# emmc.net
KiCad netlist of a schematic drawn in Altium Designer
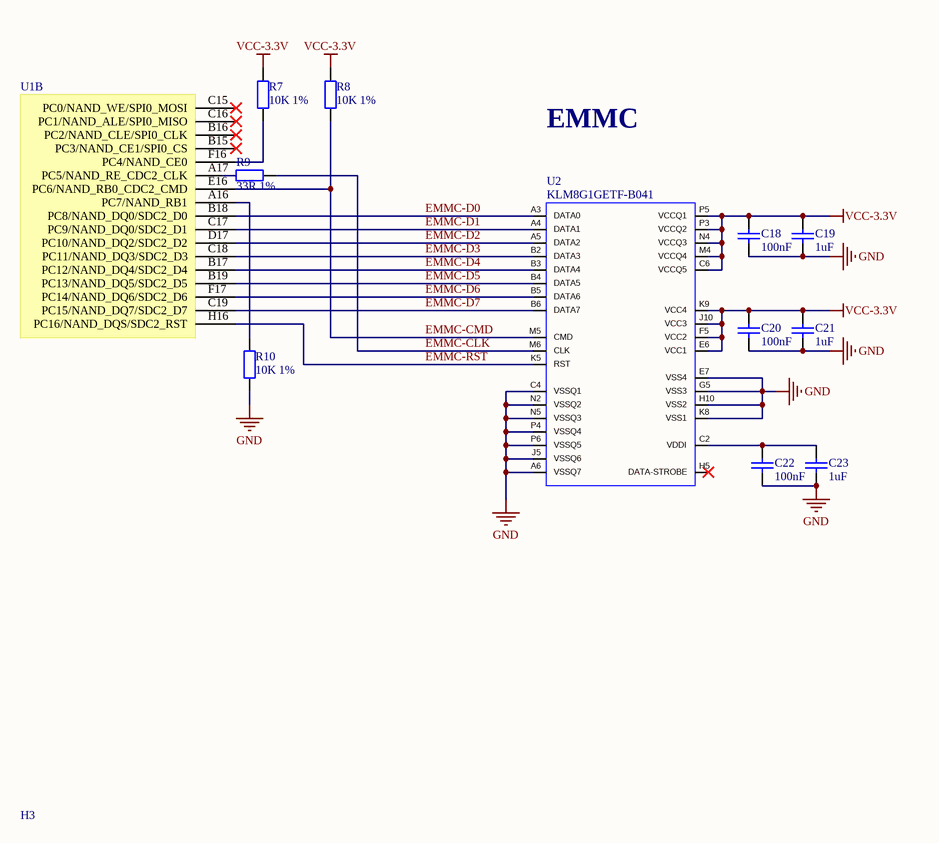
[diagram p0: emmc.SchDoc]

(export (version "E")
  (design (tool "Eeschema 10.0.6"))
  (components
    (comp (ref "C18")
      (value "100nF")
      (footprint "0402_C")
      (description "smd capacitor")
      (libsource (lib "Schlib") (part "CAP-SMD"))
    )
    (comp (ref "C19")
      (value "1uF")
      (footprint "0402_C")
      (description "smd capacitor")
      (libsource (lib "Schlib") (part "CAP-SMD"))
    )
    (comp (ref "C20")
      (value "100nF")
      (footprint "0402_C")
      (description "smd capacitor")
      (libsource (lib "Schlib") (part "CAP-SMD"))
    )
    (comp (ref "C21")
      (value "1uF")
      (footprint "0402_C")
      (description "smd capacitor")
      (libsource (lib "Schlib") (part "CAP-SMD"))
    )
    (comp (ref "C22")
      (value "100nF")
      (footprint "0402_C")
      (description "smd capacitor")
      (libsource (lib "Schlib") (part "CAP-SMD"))
    )
    (comp (ref "C23")
      (value "1uF")
      (footprint "0402_C")
      (description "smd capacitor")
      (libsource (lib "Schlib") (part "CAP-SMD"))
    )
    (comp (ref "R7")
      (value "10K 1%")
      (footprint "0402_R")
      (description "smd resistor")
      (libsource (lib "Schlib") (part "RES-SMD"))
    )
    (comp (ref "R8")
      (value "10K 1%")
      (footprint "0402_R")
      (description "smd resistor")
      (libsource (lib "Schlib") (part "RES-SMD"))
    )
    (comp (ref "R9")
      (value "33R 1%")
      (footprint "0402_R")
      (description "smd resistor")
      (libsource (lib "") (part "RES-SMD_1"))
    )
    (comp (ref "R10")
      (value "10K 1%")
      (footprint "0402_R")
      (description "smd resistor")
      (libsource (lib "Schlib") (part "RES-SMD"))
    )
    (comp (ref "U1")
      (value "H3")
      (footprint "allwinner-h3")
      (description "CPU")
      (libsource (lib "Schlib") (part "H3_CPU"))
    )
    (comp (ref "U2")
      (value "KLM8G1GETF-B041")
      (footprint "KLM8G1GETF-B041")
      (description "EMMC 8G")
      (libsource (lib "Schlib") (part "KLM8G1GEND-B031"))
    )
  )
  (nets
    (net (code "1") (name "/EMMC-CLK") (class "Default")
      (node (ref "R9") (pin "2") (pinfunction "2_2") (pintype "passive"))
      (node (ref "U2") (pin "M6") (pinfunction "CLK_M6") (pintype "passive"))
    )
    (net (code "2") (name "/EMMC-CMD") (class "Default")
      (node (ref "R8") (pin "2") (pinfunction "2_2") (pintype "passive"))
      (node (ref "U1") (pin "E16") (pinfunction "PC6/NAND_RB0_CDC2_CMD_E16") (pintype "passive"))
      (node (ref "U2") (pin "M5") (pinfunction "CMD_M5") (pintype "passive"))
    )
    (net (code "3") (name "/EMMC-D0") (class "Default")
      (node (ref "U1") (pin "B18") (pinfunction "PC8/NAND_DQ0/SDC2_D0_B18") (pintype "passive"))
      (node (ref "U2") (pin "A3") (pinfunction "DATA0_A3") (pintype "passive"))
    )
    (net (code "4") (name "/EMMC-D1") (class "Default")
      (node (ref "U1") (pin "C17") (pinfunction "PC9/NAND_DQ0/SDC2_D1_C17") (pintype "passive"))
      (node (ref "U2") (pin "A4") (pinfunction "DATA1_A4") (pintype "passive"))
    )
    (net (code "5") (name "/EMMC-D2") (class "Default")
      (node (ref "U1") (pin "D17") (pinfunction "PC10/NAND_DQ2/SDC2_D2_D17") (pintype "passive"))
      (node (ref "U2") (pin "A5") (pinfunction "DATA2_A5") (pintype "passive"))
    )
    (net (code "6") (name "/EMMC-D3") (class "Default")
      (node (ref "U1") (pin "C18") (pinfunction "PC11/NAND_DQ3/SDC2_D3_C18") (pintype "passive"))
      (node (ref "U2") (pin "B2") (pinfunction "DATA3_B2") (pintype "passive"))
    )
    (net (code "7") (name "/EMMC-D4") (class "Default")
      (node (ref "U1") (pin "B17") (pinfunction "PC12/NAND_DQ4/SDC2_D4_B17") (pintype "passive"))
      (node (ref "U2") (pin "B3") (pinfunction "DATA4_B3") (pintype "passive"))
    )
    (net (code "8") (name "/EMMC-D5") (class "Default")
      (node (ref "U1") (pin "B19") (pinfunction "PC13/NAND_DQ5/SDC2_D5_B19") (pintype "passive"))
      (node (ref "U2") (pin "B4") (pinfunction "DATA5_B4") (pintype "passive"))
    )
    (net (code "9") (name "/EMMC-D6") (class "Default")
      (node (ref "U1") (pin "F17") (pinfunction "PC14/NAND_DQ6/SDC2_D6_F17") (pintype "passive"))
      (node (ref "U2") (pin "B5") (pinfunction "DATA6_B5") (pintype "passive"))
    )
    (net (code "10") (name "/EMMC-D7") (class "Default")
      (node (ref "U1") (pin "C19") (pinfunction "PC15/NAND_DQ7/SDC2_D7_C19") (pintype "passive"))
      (node (ref "U2") (pin "B6") (pinfunction "DATA7_B6") (pintype "passive"))
    )
    (net (code "11") (name "/EMMC-RST") (class "Default")
      (node (ref "U1") (pin "H16") (pinfunction "PC16/NAND_DQS/SDC2_RST_H16") (pintype "passive"))
      (node (ref "U2") (pin "K5") (pinfunction "RST_K5") (pintype "passive"))
    )
    (net (code "12") (name "GND") (class "Default")
      (node (ref "C18") (pin "2") (pintype "passive"))
      (node (ref "C19") (pin "2") (pintype "passive"))
      (node (ref "C20") (pin "2") (pintype "passive"))
      (node (ref "C21") (pin "2") (pintype "passive"))
      (node (ref "C22") (pin "2") (pintype "passive"))
      (node (ref "C23") (pin "2") (pintype "passive"))
      (node (ref "R10") (pin "2") (pinfunction "2_2") (pintype "passive"))
      (node (ref "U2") (pin "A6") (pinfunction "VSSQ7_A6") (pintype "passive"))
      (node (ref "U2") (pin "C4") (pinfunction "VSSQ1_C4") (pintype "passive"))
      (node (ref "U2") (pin "E7") (pinfunction "VSS4_E7") (pintype "passive"))
      (node (ref "U2") (pin "G5") (pinfunction "VSS3_G5") (pintype "passive"))
      (node (ref "U2") (pin "H10") (pinfunction "VSS2_H10") (pintype "passive"))
      (node (ref "U2") (pin "J5") (pinfunction "VSSQ6_J5") (pintype "passive"))
      (node (ref "U2") (pin "K8") (pinfunction "VSS1_K8") (pintype "passive"))
      (node (ref "U2") (pin "N2") (pinfunction "VSSQ2_N2") (pintype "passive"))
      (node (ref "U2") (pin "N5") (pinfunction "VSSQ3_N5") (pintype "passive"))
      (node (ref "U2") (pin "P4") (pinfunction "VSSQ4_P4") (pintype "passive"))
      (node (ref "U2") (pin "P6") (pinfunction "VSSQ5_P6") (pintype "passive"))
    )
    (net (code "13") (name "Net-(U1B-PC4{slash}NAND_CE0)") (class "Default")
      (node (ref "R7") (pin "2") (pinfunction "2_2") (pintype "passive"))
      (node (ref "U1") (pin "F16") (pinfunction "PC4/NAND_CE0_F16") (pintype "passive"))
    )
    (net (code "14") (name "Net-(U1B-PC5{slash}NAND_RE_CDC2_CLK)") (class "Default")
      (node (ref "R9") (pin "1") (pinfunction "1_1") (pintype "passive"))
      (node (ref "U1") (pin "A17") (pinfunction "PC5/NAND_RE_CDC2_CLK_A17") (pintype "passive"))
    )
    (net (code "15") (name "Net-(U1B-PC7{slash}NAND_RB1)") (class "Default")
      (node (ref "R10") (pin "1") (pinfunction "1_1") (pintype "passive"))
      (node (ref "U1") (pin "A16") (pinfunction "PC7/NAND_RB1_A16") (pintype "passive"))
    )
    (net (code "16") (name "Net-(U2-VDDI)") (class "Default")
      (node (ref "C22") (pin "1") (pintype "passive"))
      (node (ref "C23") (pin "1") (pintype "passive"))
      (node (ref "U2") (pin "C2") (pinfunction "VDDI_C2") (pintype "passive"))
    )
    (net (code "17") (name "VCC-3.3V") (class "Default")
      (node (ref "C18") (pin "1") (pintype "passive"))
      (node (ref "C19") (pin "1") (pintype "passive"))
      (node (ref "C20") (pin "1") (pintype "passive"))
      (node (ref "C21") (pin "1") (pintype "passive"))
      (node (ref "R7") (pin "1") (pinfunction "1_1") (pintype "passive"))
      (node (ref "R8") (pin "1") (pinfunction "1_1") (pintype "passive"))
      (node (ref "U2") (pin "C6") (pinfunction "VCCQ5_C6") (pintype "passive"))
      (node (ref "U2") (pin "E6") (pinfunction "VCC1_E6") (pintype "passive"))
      (node (ref "U2") (pin "F5") (pinfunction "VCC2_F5") (pintype "passive"))
      (node (ref "U2") (pin "J10") (pinfunction "VCC3_J10") (pintype "passive"))
      (node (ref "U2") (pin "K9") (pinfunction "VCC4_K9") (pintype "passive"))
      (node (ref "U2") (pin "M4") (pinfunction "VCCQ4_M4") (pintype "passive"))
      (node (ref "U2") (pin "N4") (pinfunction "VCCQ3_N4") (pintype "passive"))
      (node (ref "U2") (pin "P3") (pinfunction "VCCQ2_P3") (pintype "passive"))
      (node (ref "U2") (pin "P5") (pinfunction "VCCQ1_P5") (pintype "passive"))
    )
    (net (code "18") (name "unconnected-(U1B-PC0{slash}NAND_WE{slash}SPI0_MOSI-PadC15)") (class "Default")
      (node (ref "U1") (pin "C15") (pinfunction "PC0/NAND_WE/SPI0_MOSI_C15") (pintype "passive+no_connect"))
    )
    (net (code "19") (name "unconnected-(U1B-PC1{slash}NAND_ALE{slash}SPI0_MISO-PadC16)") (class "Default")
      (node (ref "U1") (pin "C16") (pinfunction "PC1/NAND_ALE/SPI0_MISO_C16") (pintype "passive+no_connect"))
    )
    (net (code "20") (name "unconnected-(U1B-PC2{slash}NAND_CLE{slash}SPI0_CLK-PadB16)") (class "Default")
      (node (ref "U1") (pin "B16") (pinfunction "PC2/NAND_CLE/SPI0_CLK_B16") (pintype "passive+no_connect"))
    )
    (net (code "21") (name "unconnected-(U1B-PC3{slash}NAND_CE1{slash}SPI0_CS-PadB15)") (class "Default")
      (node (ref "U1") (pin "B15") (pinfunction "PC3/NAND_CE1/SPI0_CS_B15") (pintype "passive+no_connect"))
    )
    (net (code "22") (name "unconnected-(U2-DATA-STROBE-PadH5)") (class "Default")
      (node (ref "U2") (pin "H5") (pinfunction "DATA-STROBE_H5") (pintype "passive+no_connect"))
    )
  )
)
